# LowCurrentSwitch.net
KiCad netlist of a schematic drawn in Altium Designer
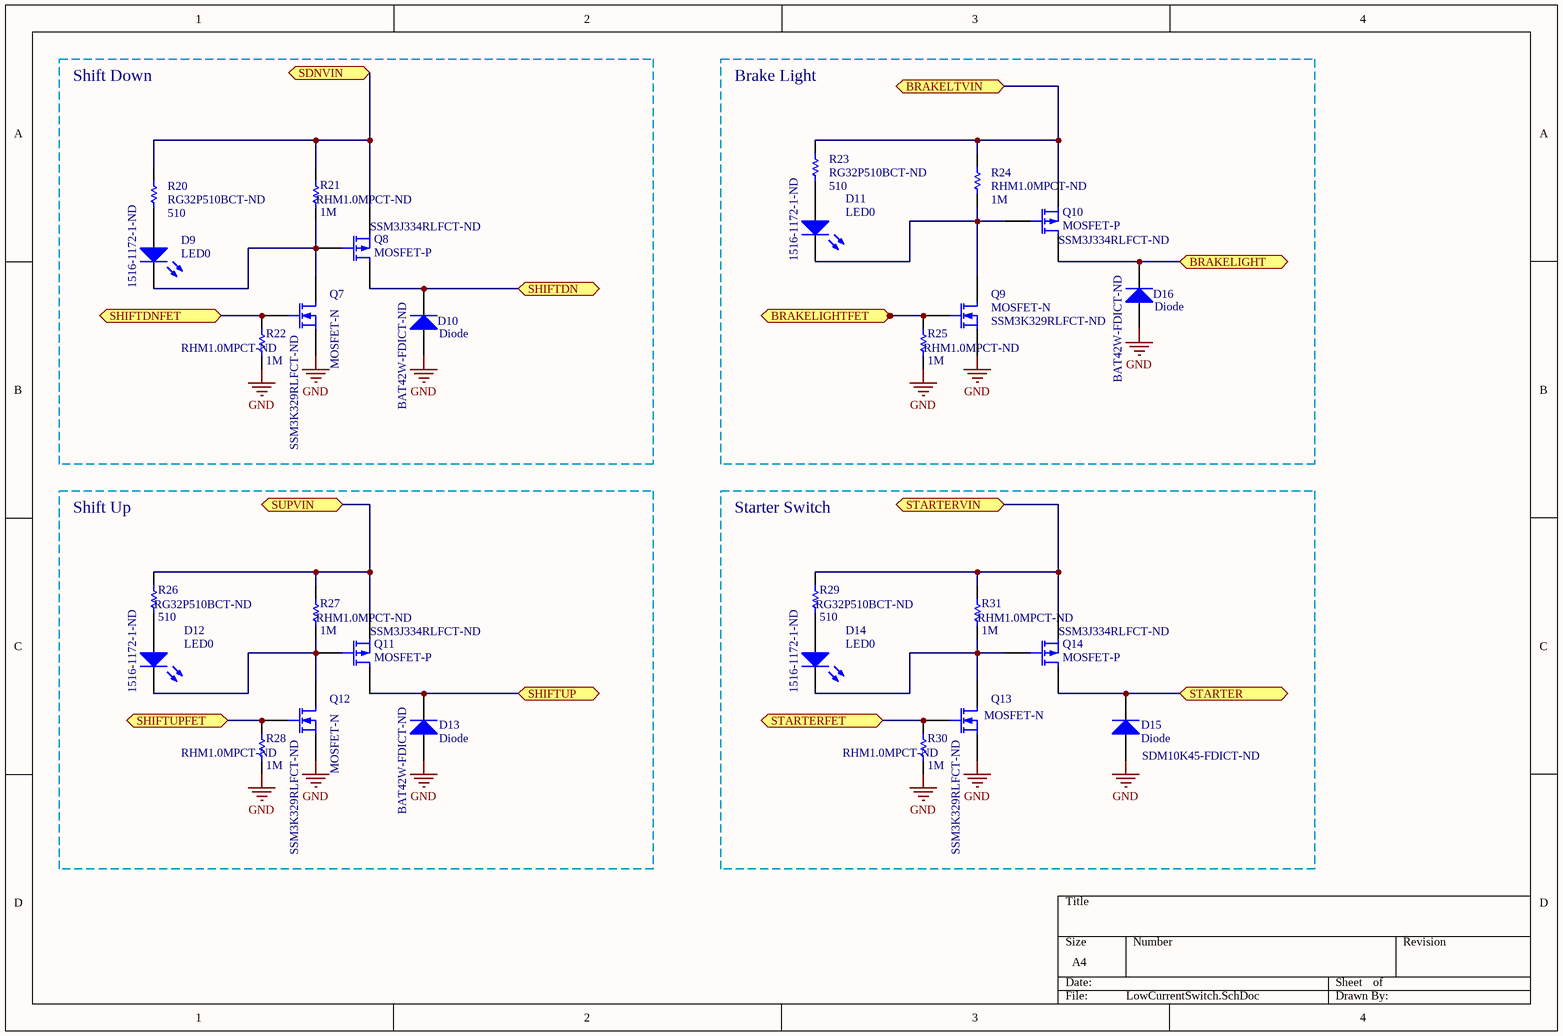
[diagram p0: LowCurrentSwitch.SchDoc]

(export (version "E")
  (design (tool "Eeschema 10.0.6"))
  (components
    (comp (ref "D9")
      (value "LED0")
      (footprint "C1206")
      (description "Typical INFRARED GaAs LED")
      (fields
        (field (name "SUPPLIER PART NUMBER 1") "1516-1172-1-ND")
        (field (name "PUBLISHER") "Altium Limited")
      )
      (libsource (lib "Miscellaneous Devices") (part "LED0"))
    )
    (comp (ref "D10")
      (value "Diode")
      (footprint "sod-123")
      (description "Default Diode")
      (fields
        (field (name "SUPPLIER PART NUMBER 1") "BAT42W-FDICT-ND")
        (field (name "PUBLISHER") "Altium Limited")
      )
      (libsource (lib "Miscellaneous Devices") (part "Diode"))
    )
    (comp (ref "D11")
      (value "LED0")
      (footprint "C1206")
      (description "Typical INFRARED GaAs LED")
      (fields
        (field (name "SUPPLIER PART NUMBER 1") "1516-1172-1-ND")
        (field (name "PUBLISHER") "Altium Limited")
      )
      (libsource (lib "Miscellaneous Devices") (part "LED0"))
    )
    (comp (ref "D12")
      (value "LED0")
      (footprint "C1206")
      (description "Typical INFRARED GaAs LED")
      (fields
        (field (name "SUPPLIER PART NUMBER 1") "1516-1172-1-ND")
        (field (name "PUBLISHER") "Altium Limited")
      )
      (libsource (lib "Miscellaneous Devices") (part "LED0"))
    )
    (comp (ref "D13")
      (value "Diode")
      (footprint "sod-123")
      (description "Default Diode")
      (fields
        (field (name "SUPPLIER PART NUMBER 1") "BAT42W-FDICT-ND")
        (field (name "PUBLISHER") "Altium Limited")
      )
      (libsource (lib "Miscellaneous Devices") (part "Diode"))
    )
    (comp (ref "D14")
      (value "LED0")
      (footprint "C1206")
      (description "Typical INFRARED GaAs LED")
      (fields
        (field (name "SUPPLIER PART NUMBER 1") "1516-1172-1-ND")
        (field (name "PUBLISHER") "Altium Limited")
      )
      (libsource (lib "Miscellaneous Devices") (part "LED0"))
    )
    (comp (ref "D15")
      (value "Diode")
      (footprint "SOD-323")
      (description "Default Diode")
      (fields
        (field (name "SUPPLIER PART NUMBER 1") "SDM10K45-FDICT-ND")
        (field (name "PUBLISHER") "Altium Limited")
      )
      (libsource (lib "Miscellaneous Devices") (part "Diode"))
    )
    (comp (ref "D16")
      (value "Diode")
      (footprint "sod-123")
      (description "Default Diode")
      (fields
        (field (name "SUPPLIER PART NUMBER 1") "BAT42W-FDICT-ND")
        (field (name "PUBLISHER") "Altium Limited")
      )
      (libsource (lib "Miscellaneous Devices") (part "Diode"))
    )
    (comp (ref "Q7")
      (value "MOSFET-N")
      (footprint "SOT23f")
      (description "N-Channel MOSFET")
      (fields
        (field (name "SUPPLIER PART NUMBER 1") "SSM3K329RLFCT-ND")
        (field (name "PUBLISHER") "Altium Limited")
      )
      (libsource (lib "Miscellaneous Devices") (part "MOSFET-N"))
    )
    (comp (ref "Q8")
      (value "MOSFET-P")
      (footprint "SOT23f")
      (description "P-Channel MOSFET")
      (fields
        (field (name "SUPPLIER PART NUMBER 1") "SSM3J334RLFCT-ND")
        (field (name "PUBLISHER") "Altium Limited")
      )
      (libsource (lib "Miscellaneous Devices") (part "MOSFET-P"))
    )
    (comp (ref "Q9")
      (value "MOSFET-N")
      (footprint "SOT23f")
      (description "N-Channel MOSFET")
      (fields
        (field (name "SUPPLIER PART NUMBER 1") "SSM3K329RLFCT-ND")
        (field (name "PUBLISHER") "Altium Limited")
      )
      (libsource (lib "Miscellaneous Devices") (part "MOSFET-N"))
    )
    (comp (ref "Q10")
      (value "MOSFET-P")
      (footprint "SOT23f")
      (description "P-Channel MOSFET")
      (fields
        (field (name "SUPPLIER PART NUMBER 1") "SSM3J334RLFCT-ND")
        (field (name "PUBLISHER") "Altium Limited")
      )
      (libsource (lib "Miscellaneous Devices") (part "MOSFET-P"))
    )
    (comp (ref "Q11")
      (value "MOSFET-P")
      (footprint "SOT23f")
      (description "P-Channel MOSFET")
      (fields
        (field (name "SUPPLIER PART NUMBER 1") "SSM3J334RLFCT-ND")
        (field (name "PUBLISHER") "Altium Limited")
      )
      (libsource (lib "Miscellaneous Devices") (part "MOSFET-P"))
    )
    (comp (ref "Q12")
      (value "MOSFET-N")
      (footprint "SOT23f")
      (description "N-Channel MOSFET")
      (fields
        (field (name "SUPPLIER PART NUMBER 1") "SSM3K329RLFCT-ND")
        (field (name "PUBLISHER") "Altium Limited")
      )
      (libsource (lib "Miscellaneous Devices") (part "MOSFET-N"))
    )
    (comp (ref "Q13")
      (value "MOSFET-N")
      (footprint "SOT23f")
      (description "N-Channel MOSFET")
      (fields
        (field (name "SUPPLIER PART NUMBER 1") "SSM3K329RLFCT-ND")
        (field (name "PUBLISHER") "Altium Limited")
      )
      (libsource (lib "Miscellaneous Devices") (part "MOSFET-N"))
    )
    (comp (ref "Q14")
      (value "MOSFET-P")
      (footprint "SOT23f")
      (description "P-Channel MOSFET")
      (fields
        (field (name "SUPPLIER PART NUMBER 1") "SSM3J334RLFCT-ND")
        (field (name "PUBLISHER") "Altium Limited")
      )
      (libsource (lib "Miscellaneous Devices") (part "MOSFET-P"))
    )
    (comp (ref "R20")
      (value "510")
      (footprint "C1206")
      (description "Resistor")
      (fields
        (field (name "SUPPLIER PART NUMBER 1") "RG32P510BCT-ND")
        (field (name "Comment") "1206")
        (field (name "PUBLISHER") "Altium Limited")
      )
      (libsource (lib "Miscellaneous Devices") (part "Res1"))
    )
    (comp (ref "R21")
      (value "1M")
      (footprint "C1206")
      (description "Resistor")
      (fields
        (field (name "SUPPLIER PART NUMBER 1") "RHM1.0MPCT-ND")
        (field (name "Comment") "1206")
        (field (name "PUBLISHER") "Altium Limited")
      )
      (libsource (lib "Miscellaneous Devices") (part "Res1"))
    )
    (comp (ref "R22")
      (value "1M")
      (footprint "C1206")
      (description "Resistor")
      (fields
        (field (name "SUPPLIER PART NUMBER 1") "RHM1.0MPCT-ND")
        (field (name "Comment") "1206")
        (field (name "PUBLISHER") "Altium Limited")
      )
      (libsource (lib "Miscellaneous Devices") (part "Res1"))
    )
    (comp (ref "R23")
      (value "510")
      (footprint "C1206")
      (description "Resistor")
      (fields
        (field (name "SUPPLIER PART NUMBER 1") "RG32P510BCT-ND")
        (field (name "Comment") "1206")
        (field (name "PUBLISHER") "Altium Limited")
      )
      (libsource (lib "Miscellaneous Devices") (part "Res1"))
    )
    (comp (ref "R24")
      (value "1M")
      (footprint "C1206")
      (description "Resistor")
      (fields
        (field (name "SUPPLIER PART NUMBER 1") "RHM1.0MPCT-ND")
        (field (name "Comment") "Res1")
        (field (name "PUBLISHER") "Altium Limited")
      )
      (libsource (lib "Miscellaneous Devices") (part "Res1"))
    )
    (comp (ref "R25")
      (value "1M")
      (footprint "C1206")
      (description "Resistor")
      (fields
        (field (name "SUPPLIER PART NUMBER 1") "RHM1.0MPCT-ND")
        (field (name "Comment") "Res1")
        (field (name "PUBLISHER") "Altium Limited")
      )
      (libsource (lib "Miscellaneous Devices") (part "Res1"))
    )
    (comp (ref "R26")
      (value "510")
      (footprint "C1206")
      (description "Resistor")
      (fields
        (field (name "SUPPLIER PART NUMBER 1") "RG32P510BCT-ND")
        (field (name "Comment") "1206")
        (field (name "PUBLISHER") "Altium Limited")
      )
      (libsource (lib "Miscellaneous Devices") (part "Res1"))
    )
    (comp (ref "R27")
      (value "1M")
      (footprint "C1206")
      (description "Resistor")
      (fields
        (field (name "SUPPLIER PART NUMBER 1") "RHM1.0MPCT-ND")
        (field (name "Comment") "1206")
        (field (name "PUBLISHER") "Altium Limited")
      )
      (libsource (lib "Miscellaneous Devices") (part "Res1"))
    )
    (comp (ref "R28")
      (value "1M")
      (footprint "C1206")
      (description "Resistor")
      (fields
        (field (name "SUPPLIER PART NUMBER 1") "RHM1.0MPCT-ND")
        (field (name "Comment") "1206")
        (field (name "PUBLISHER") "Altium Limited")
      )
      (libsource (lib "Miscellaneous Devices") (part "Res1"))
    )
    (comp (ref "R29")
      (value "510")
      (footprint "C1206")
      (description "Resistor")
      (fields
        (field (name "SUPPLIER PART NUMBER 1") "RG32P510BCT-ND")
        (field (name "Comment") "1206")
        (field (name "PUBLISHER") "Altium Limited")
      )
      (libsource (lib "Miscellaneous Devices") (part "Res1"))
    )
    (comp (ref "R30")
      (value "1M")
      (footprint "C1206")
      (description "Resistor")
      (fields
        (field (name "SUPPLIER PART NUMBER 1") "RHM1.0MPCT-ND")
        (field (name "Comment") "1206")
        (field (name "PUBLISHER") "Altium Limited")
      )
      (libsource (lib "Miscellaneous Devices") (part "Res1"))
    )
    (comp (ref "R31")
      (value "1M")
      (footprint "C1206")
      (description "Resistor")
      (fields
        (field (name "SUPPLIER PART NUMBER 1") "RHM1.0MPCT-ND")
        (field (name "Comment") "1206")
        (field (name "PUBLISHER") "Altium Limited")
      )
      (libsource (lib "Miscellaneous Devices") (part "Res1"))
    )
  )
  (nets
    (net (code "1") (name "/BRAKELIGHT") (class "Default")
      (node (ref "D16") (pin "2") (pinfunction "K_2") (pintype "passive"))
      (node (ref "Q10") (pin "1") (pinfunction "D_1") (pintype "passive"))
    )
    (net (code "2") (name "/BRAKELIGHTFET") (class "Default")
      (node (ref "Q9") (pin "2") (pinfunction "G_2") (pintype "passive"))
      (node (ref "R25") (pin "2") (pinfunction "2_2") (pintype "passive"))
    )
    (net (code "3") (name "/BRAKELTVIN") (class "Default")
      (node (ref "Q10") (pin "3") (pinfunction "S_3") (pintype "passive"))
      (node (ref "R23") (pin "1") (pinfunction "1_1") (pintype "passive"))
      (node (ref "R24") (pin "2") (pinfunction "2_2") (pintype "passive"))
    )
    (net (code "4") (name "/SDNVIN") (class "Default")
      (node (ref "Q8") (pin "3") (pinfunction "S_3") (pintype "passive"))
      (node (ref "R20") (pin "1") (pinfunction "1_1") (pintype "passive"))
      (node (ref "R21") (pin "2") (pinfunction "2_2") (pintype "passive"))
    )
    (net (code "5") (name "/SHIFTDN") (class "Default")
      (node (ref "D10") (pin "2") (pinfunction "K_2") (pintype "passive"))
      (node (ref "Q8") (pin "1") (pinfunction "D_1") (pintype "passive"))
    )
    (net (code "6") (name "/SHIFTDNFET") (class "Default")
      (node (ref "Q7") (pin "2") (pinfunction "G_2") (pintype "passive"))
      (node (ref "R22") (pin "2") (pinfunction "2_2") (pintype "passive"))
    )
    (net (code "7") (name "/SHIFTUP") (class "Default")
      (node (ref "D13") (pin "2") (pinfunction "K_2") (pintype "passive"))
      (node (ref "Q11") (pin "1") (pinfunction "D_1") (pintype "passive"))
    )
    (net (code "8") (name "/SHIFTUPFET") (class "Default")
      (node (ref "Q12") (pin "2") (pinfunction "G_2") (pintype "passive"))
      (node (ref "R28") (pin "2") (pinfunction "2_2") (pintype "passive"))
    )
    (net (code "9") (name "/STARTER") (class "Default")
      (node (ref "D15") (pin "2") (pinfunction "K_2") (pintype "passive"))
      (node (ref "Q14") (pin "1") (pinfunction "D_1") (pintype "passive"))
    )
    (net (code "10") (name "/STARTERFET") (class "Default")
      (node (ref "Q13") (pin "2") (pinfunction "G_2") (pintype "passive"))
      (node (ref "R30") (pin "2") (pinfunction "2_2") (pintype "passive"))
    )
    (net (code "11") (name "/STARTERVIN") (class "Default")
      (node (ref "Q14") (pin "3") (pinfunction "S_3") (pintype "passive"))
      (node (ref "R29") (pin "1") (pinfunction "1_1") (pintype "passive"))
      (node (ref "R31") (pin "2") (pinfunction "2_2") (pintype "passive"))
    )
    (net (code "12") (name "/SUPVIN") (class "Default")
      (node (ref "Q11") (pin "3") (pinfunction "S_3") (pintype "passive"))
      (node (ref "R26") (pin "1") (pinfunction "1_1") (pintype "passive"))
      (node (ref "R27") (pin "2") (pinfunction "2_2") (pintype "passive"))
    )
    (net (code "13") (name "GND") (class "Default")
      (node (ref "D10") (pin "1") (pinfunction "A_1") (pintype "passive"))
      (node (ref "D13") (pin "1") (pinfunction "A_1") (pintype "passive"))
      (node (ref "D15") (pin "1") (pinfunction "A_1") (pintype "passive"))
      (node (ref "D16") (pin "1") (pinfunction "A_1") (pintype "passive"))
      (node (ref "Q12") (pin "3") (pinfunction "S_3") (pintype "passive"))
      (node (ref "Q13") (pin "3") (pinfunction "S_3") (pintype "passive"))
      (node (ref "Q7") (pin "3") (pinfunction "S_3") (pintype "passive"))
      (node (ref "Q9") (pin "3") (pinfunction "S_3") (pintype "passive"))
      (node (ref "R22") (pin "1") (pinfunction "1_1") (pintype "passive"))
      (node (ref "R25") (pin "1") (pinfunction "1_1") (pintype "passive"))
      (node (ref "R28") (pin "1") (pinfunction "1_1") (pintype "passive"))
      (node (ref "R30") (pin "1") (pinfunction "1_1") (pintype "passive"))
    )
    (net (code "14") (name "Net-(D9-A)") (class "Default")
      (node (ref "D9") (pin "1") (pinfunction "A_1") (pintype "passive"))
      (node (ref "R20") (pin "2") (pinfunction "2_2") (pintype "passive"))
    )
    (net (code "15") (name "Net-(D9-K)") (class "Default")
      (node (ref "D9") (pin "2") (pinfunction "K_2") (pintype "passive"))
      (node (ref "Q7") (pin "1") (pinfunction "D_1") (pintype "passive"))
      (node (ref "Q8") (pin "2") (pinfunction "G_2") (pintype "passive"))
      (node (ref "R21") (pin "1") (pinfunction "1_1") (pintype "passive"))
    )
    (net (code "16") (name "Net-(D11-A)") (class "Default")
      (node (ref "D11") (pin "1") (pinfunction "A_1") (pintype "passive"))
      (node (ref "R23") (pin "2") (pinfunction "2_2") (pintype "passive"))
    )
    (net (code "17") (name "Net-(D11-K)") (class "Default")
      (node (ref "D11") (pin "2") (pinfunction "K_2") (pintype "passive"))
      (node (ref "Q10") (pin "2") (pinfunction "G_2") (pintype "passive"))
      (node (ref "Q9") (pin "1") (pinfunction "D_1") (pintype "passive"))
      (node (ref "R24") (pin "1") (pinfunction "1_1") (pintype "passive"))
    )
    (net (code "18") (name "Net-(D12-A)") (class "Default")
      (node (ref "D12") (pin "1") (pinfunction "A_1") (pintype "passive"))
      (node (ref "R26") (pin "2") (pinfunction "2_2") (pintype "passive"))
    )
    (net (code "19") (name "Net-(D12-K)") (class "Default")
      (node (ref "D12") (pin "2") (pinfunction "K_2") (pintype "passive"))
      (node (ref "Q11") (pin "2") (pinfunction "G_2") (pintype "passive"))
      (node (ref "Q12") (pin "1") (pinfunction "D_1") (pintype "passive"))
      (node (ref "R27") (pin "1") (pinfunction "1_1") (pintype "passive"))
    )
    (net (code "20") (name "Net-(D14-A)") (class "Default")
      (node (ref "D14") (pin "1") (pinfunction "A_1") (pintype "passive"))
      (node (ref "R29") (pin "2") (pinfunction "2_2") (pintype "passive"))
    )
    (net (code "21") (name "Net-(D14-K)") (class "Default")
      (node (ref "D14") (pin "2") (pinfunction "K_2") (pintype "passive"))
      (node (ref "Q13") (pin "1") (pinfunction "D_1") (pintype "passive"))
      (node (ref "Q14") (pin "2") (pinfunction "G_2") (pintype "passive"))
      (node (ref "R31") (pin "1") (pinfunction "1_1") (pintype "passive"))
    )
  )
)
